# Hardware.net
KiCad netlist of a schematic drawn in EAGLE
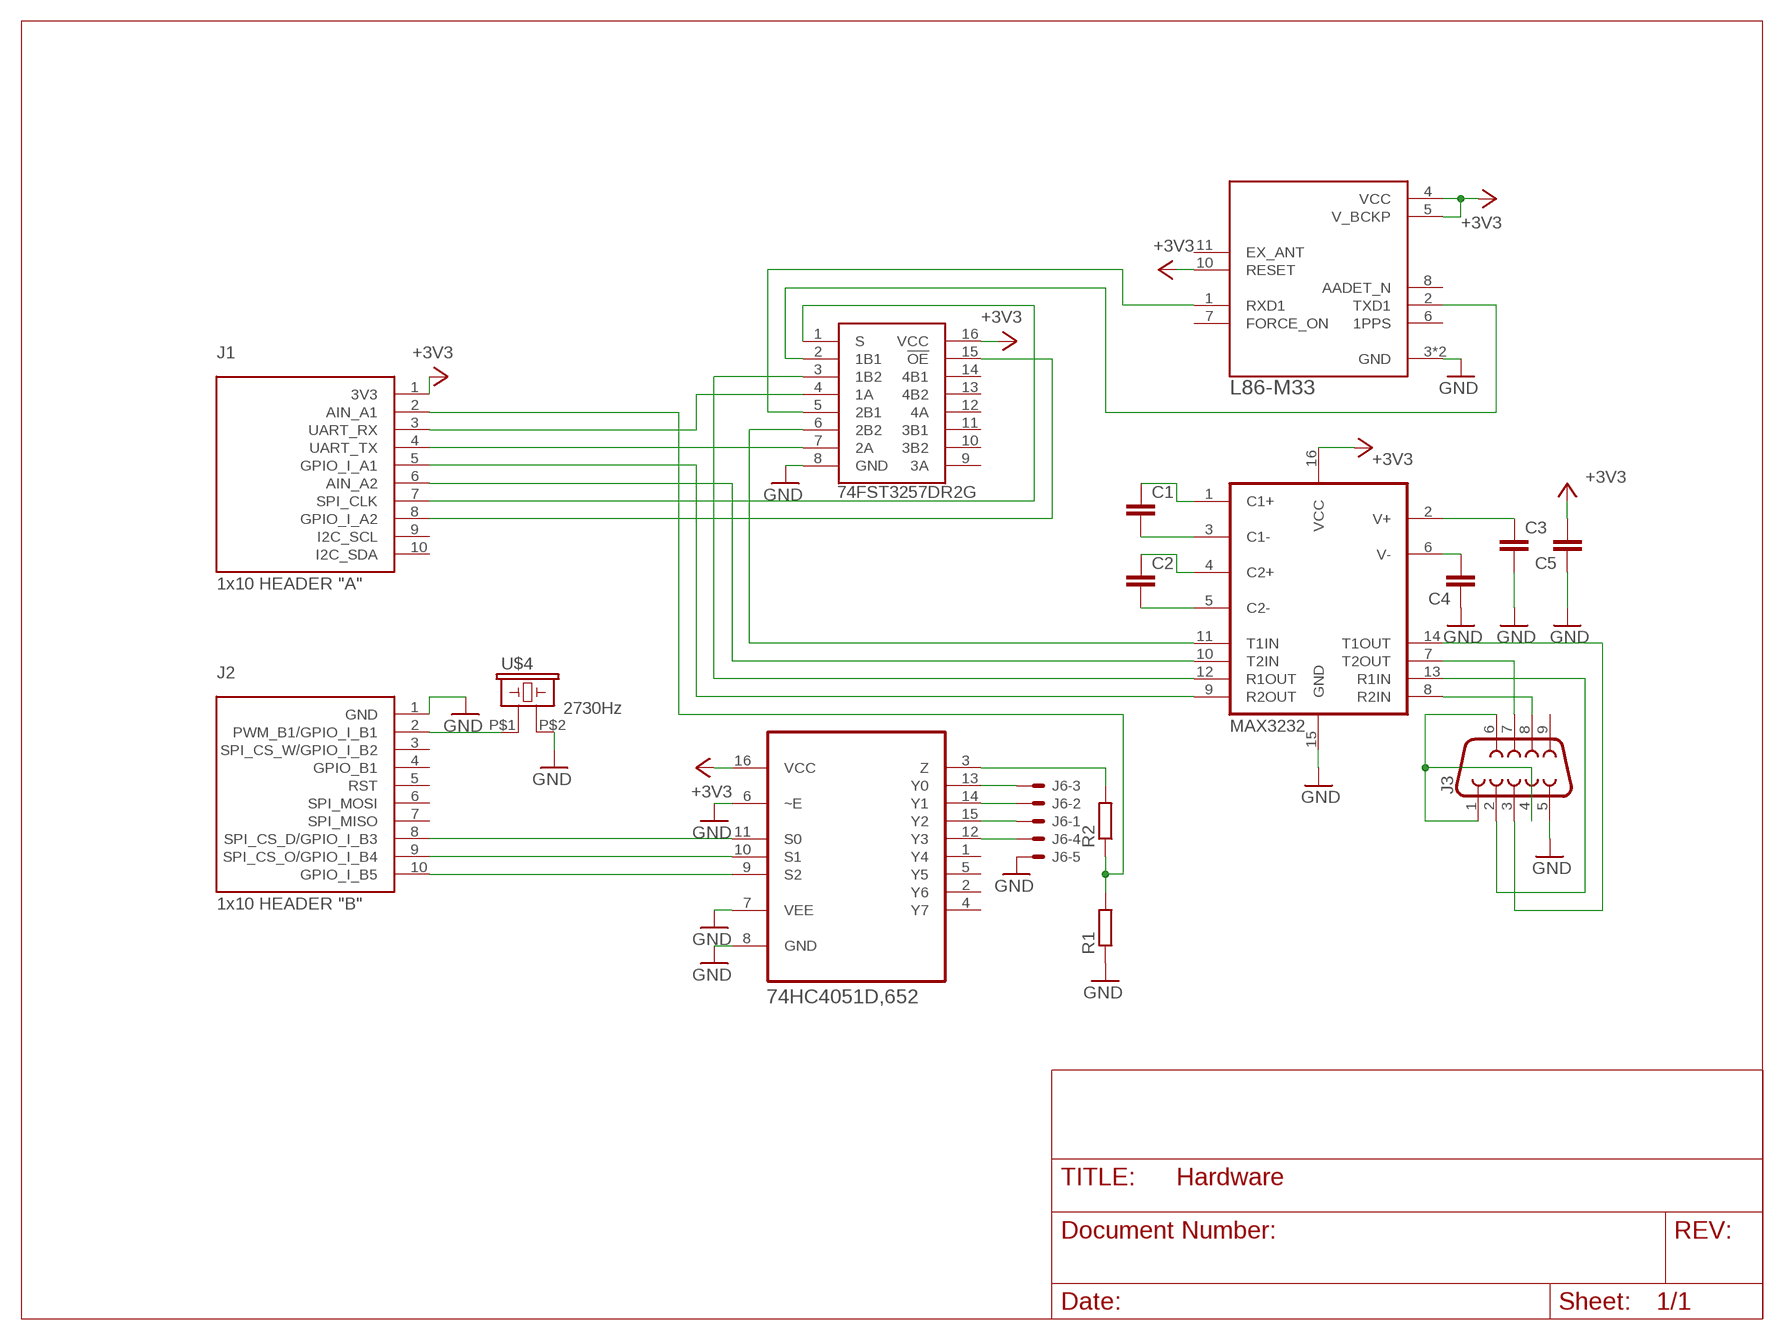
[diagram p0: schematic, sheet 1]

(export (version "E")
  (design (tool "Eeschema 10.0.6"))
  (components
    (comp (ref "C1")
      (value "C-EUC0805K")
      (footprint "eagle-import:C0805K")
      (libsource (lib "eagle-import") (part "C-EUC0805K"))
    )
    (comp (ref "C2")
      (value "C-EUC0805K")
      (footprint "eagle-import:C0805K")
      (libsource (lib "eagle-import") (part "C-EUC0805K"))
    )
    (comp (ref "C3")
      (value "C-EUC0805K")
      (footprint "eagle-import:C0805K")
      (libsource (lib "eagle-import") (part "C-EUC0805K"))
    )
    (comp (ref "C4")
      (value "C-EUC0805K")
      (footprint "eagle-import:C0805K")
      (libsource (lib "eagle-import") (part "C-EUC0805K"))
    )
    (comp (ref "C5")
      (value "C-EUC0805K")
      (footprint "eagle-import:C0805K")
      (libsource (lib "eagle-import") (part "C-EUC0805K"))
    )
    (comp (ref "IC1")
      (value "74FST3257DR2G")
      (footprint "eagle-import:SOIC127P600X175-16N")
      (fields (field (name "RS_PART_NUMBER") "8009395"))
      (libsource (lib "eagle-import") (part "74FST3257DR2G"))
    )
    (comp (ref "J1")
      (value "1x10 HEADER \"A\"")
      (footprint "eagle-import:1X10")
      (libsource (lib "eagle-import") (part "HEADER-1X10-J1"))
    )
    (comp (ref "J2")
      (value "1x10 HEADER \"B\"")
      (footprint "eagle-import:1X10")
      (libsource (lib "eagle-import") (part "HEADER-1X10-J2"))
    )
    (comp (ref "J3")
      (value "DB9MALE")
      (footprint "eagle-import:DB9_MALE")
      (libsource (lib "eagle-import") (part "DB9MALE"))
    )
    (comp (ref "J6")
      (value "22-27-2051-05")
      (footprint "eagle-import:6410-05")
      (fields (field (name "MF") "MOLEX"))
      (libsource (lib "eagle-import") (part "22-?-0527-2051"))
    )
    (comp (ref "R1")
      (value "R-EU_0207/7")
      (footprint "eagle-import:0207_7")
      (libsource (lib "eagle-import") (part "R-EU_0207/7"))
    )
    (comp (ref "R2")
      (value "R-EU_0207/7")
      (footprint "eagle-import:0207_7")
      (libsource (lib "eagle-import") (part "R-EU_0207/7"))
    )
    (comp (ref "U$4")
      (value "KCVG084B16")
      (footprint "eagle-import:KCVG084B16")
      (libsource (lib "eagle-import") (part "KCVG084B16"))
    )
    (comp (ref "U1")
      (value "MAX3232")
      (footprint "eagle-import:SO16")
      (libsource (lib "eagle-import") (part "MAX2323SOIC16"))
    )
    (comp (ref "U2")
      (value "L86-M33")
      (footprint "eagle-import:SON254P1840X1840X40-12N")
      (fields (field (name "MF") "Quectel"))
      (libsource (lib "eagle-import") (part "L86-M33"))
    )
    (comp (ref "U4")
      (value "74HC4051D,652")
      (footprint "eagle-import:SOIC127P600X175-16N")
      (fields (field (name "MF") "Nexperia"))
      (libsource (lib "eagle-import") (part "74HC4051D,652"))
    )
  )
  (nets
    (net (code "1") (name "+3V3") (class "Default")
      (node (ref "C5") (pin "2") (pinfunction "2_2") (pintype "passive"))
      (node (ref "IC1") (pin "16") (pinfunction "VCC_16") (pintype "input"))
      (node (ref "J1") (pin "1") (pinfunction "3V3_1") (pintype "bidirectional"))
      (node (ref "U1") (pin "16") (pinfunction "VCC_16") (pintype "bidirectional"))
      (node (ref "U2") (pin "10") (pinfunction "RESET_10") (pintype "input"))
      (node (ref "U2") (pin "4") (pinfunction "VCC_4") (pintype "power_in"))
      (node (ref "U2") (pin "5") (pinfunction "V_BCKP_5") (pintype "power_in"))
      (node (ref "U4") (pin "16") (pinfunction "VCC_16") (pintype "power_in"))
    )
    (net (code "2") (name "GND") (class "Default")
      (node (ref "C3") (pin "2") (pinfunction "2_2") (pintype "passive"))
      (node (ref "C4") (pin "1") (pinfunction "1_1") (pintype "passive"))
      (node (ref "C5") (pin "1") (pinfunction "1_1") (pintype "passive"))
      (node (ref "IC1") (pin "8") (pinfunction "GND_8") (pintype "input"))
      (node (ref "J2") (pin "1") (pinfunction "GND_1") (pintype "bidirectional"))
      (node (ref "J3") (pin "5") (pinfunction "5_5") (pintype "passive"))
      (node (ref "J6") (pin "5") (pinfunction "S_5") (pintype "passive"))
      (node (ref "R1") (pin "1") (pinfunction "1_1") (pintype "passive"))
      (node (ref "U$4") (pin "P$2") (pinfunction "2_P$2") (pintype "passive"))
      (node (ref "U1") (pin "15") (pinfunction "GND_15") (pintype "bidirectional"))
      (node (ref "U2") (pin "12") (pinfunction "GND_12") (pintype "passive"))
      (node (ref "U2") (pin "3") (pinfunction "GND_3") (pintype "passive"))
      (node (ref "U4") (pin "6") (pinfunction "~{E}_6") (pintype "input"))
      (node (ref "U4") (pin "7") (pinfunction "VEE_7") (pintype "power_in"))
      (node (ref "U4") (pin "8") (pinfunction "GND_8") (pintype "passive"))
    )
    (net (code "3") (name "Net-(IC1-1A)") (class "Default")
      (node (ref "IC1") (pin "4") (pinfunction "1A_4") (pintype "input"))
      (node (ref "J1") (pin "3") (pinfunction "UART_RX_3") (pintype "bidirectional"))
    )
    (net (code "4") (name "Net-(IC1-1B1)") (class "Default")
      (node (ref "IC1") (pin "2") (pinfunction "1B1_2") (pintype "input"))
      (node (ref "U2") (pin "2") (pinfunction "TXD1_2") (pintype "output"))
    )
    (net (code "5") (name "Net-(IC1-1B2)") (class "Default")
      (node (ref "IC1") (pin "3") (pinfunction "1B2_3") (pintype "input"))
      (node (ref "U1") (pin "12") (pinfunction "R1OUT_12") (pintype "output"))
    )
    (net (code "6") (name "Net-(IC1-2A)") (class "Default")
      (node (ref "IC1") (pin "7") (pinfunction "2A_7") (pintype "input"))
      (node (ref "J1") (pin "4") (pinfunction "UART_TX_4") (pintype "bidirectional"))
    )
    (net (code "7") (name "Net-(IC1-2B1)") (class "Default")
      (node (ref "IC1") (pin "5") (pinfunction "2B1_5") (pintype "input"))
      (node (ref "U2") (pin "1") (pinfunction "RXD1_1") (pintype "input"))
    )
    (net (code "8") (name "Net-(IC1-2B2)") (class "Default")
      (node (ref "IC1") (pin "6") (pinfunction "2B2_6") (pintype "input"))
      (node (ref "U1") (pin "11") (pinfunction "T1IN_11") (pintype "input"))
    )
    (net (code "9") (name "Net-(IC1-S)") (class "Default")
      (node (ref "IC1") (pin "1") (pinfunction "S_1") (pintype "input"))
      (node (ref "J1") (pin "7") (pinfunction "SPI_CLK_7") (pintype "bidirectional"))
    )
    (net (code "10") (name "Net-(IC1-~{OE})") (class "Default")
      (node (ref "IC1") (pin "15") (pinfunction "~{OE}_15") (pintype "input"))
      (node (ref "J1") (pin "8") (pinfunction "GPIO_I_A2_8") (pintype "bidirectional"))
    )
    (net (code "11") (name "Net-(J1-AIN_A1)") (class "Default")
      (node (ref "J1") (pin "2") (pinfunction "AIN_A1_2") (pintype "bidirectional"))
      (node (ref "R1") (pin "2") (pinfunction "2_2") (pintype "passive"))
      (node (ref "R2") (pin "1") (pinfunction "1_1") (pintype "passive"))
    )
    (net (code "12") (name "Net-(J1-AIN_A2)") (class "Default")
      (node (ref "J1") (pin "6") (pinfunction "AIN_A2_6") (pintype "bidirectional"))
      (node (ref "U1") (pin "10") (pinfunction "T2IN_10") (pintype "input"))
    )
    (net (code "13") (name "Net-(J1-GPIO_I_A1)") (class "Default")
      (node (ref "J1") (pin "5") (pinfunction "GPIO_I_A1_5") (pintype "bidirectional"))
      (node (ref "U1") (pin "9") (pinfunction "R2OUT_9") (pintype "output"))
    )
    (net (code "14") (name "Net-(J2-GPIO_I_B5)") (class "Default")
      (node (ref "J2") (pin "10") (pinfunction "GPIO_I_B5_10") (pintype "bidirectional"))
      (node (ref "U4") (pin "9") (pinfunction "S2_9") (pintype "input"))
    )
    (net (code "15") (name "Net-(J2-PWM_B1{slash}GPIO_I_B1)") (class "Default")
      (node (ref "J2") (pin "2") (pinfunction "PWM_B1/GPIO_I_B1_2") (pintype "bidirectional"))
      (node (ref "U$4") (pin "P$1") (pinfunction "1_P$1") (pintype "passive"))
    )
    (net (code "16") (name "Net-(J2-SPI_CS_D{slash}GPIO_I_B3)") (class "Default")
      (node (ref "J2") (pin "8") (pinfunction "SPI_CS_D/GPIO_I_B3_8") (pintype "bidirectional"))
      (node (ref "U4") (pin "11") (pinfunction "S0_11") (pintype "input"))
    )
    (net (code "17") (name "Net-(J2-SPI_CS_O{slash}GPIO_I_B4)") (class "Default")
      (node (ref "J2") (pin "9") (pinfunction "SPI_CS_O/GPIO_I_B4_9") (pintype "bidirectional"))
      (node (ref "U4") (pin "10") (pinfunction "S1_10") (pintype "input"))
    )
    (net (code "18") (name "Net-(J3-Pad1)") (class "Default")
      (node (ref "J3") (pin "1") (pinfunction "1_1") (pintype "passive"))
      (node (ref "J3") (pin "4") (pinfunction "4_4") (pintype "passive"))
      (node (ref "J3") (pin "6") (pinfunction "6_6") (pintype "passive"))
    )
    (net (code "19") (name "Net-(J6A-S)") (class "Default")
      (node (ref "J6") (pin "1") (pinfunction "S_1") (pintype "passive"))
      (node (ref "U4") (pin "15") (pinfunction "Y2_15") (pintype "bidirectional"))
    )
    (net (code "20") (name "Net-(J6B-S)") (class "Default")
      (node (ref "J6") (pin "2") (pinfunction "S_2") (pintype "passive"))
      (node (ref "U4") (pin "14") (pinfunction "Y1_14") (pintype "bidirectional"))
    )
    (net (code "21") (name "Net-(J6C-S)") (class "Default")
      (node (ref "J6") (pin "3") (pinfunction "S_3") (pintype "passive"))
      (node (ref "U4") (pin "13") (pinfunction "Y0_13") (pintype "bidirectional"))
    )
    (net (code "22") (name "Net-(J6D-S)") (class "Default")
      (node (ref "J6") (pin "4") (pinfunction "S_4") (pintype "passive"))
      (node (ref "U4") (pin "12") (pinfunction "Y3_12") (pintype "bidirectional"))
    )
    (net (code "23") (name "Net-(U1-C1+)") (class "Default")
      (node (ref "C1") (pin "1") (pinfunction "1_1") (pintype "passive"))
      (node (ref "U1") (pin "1") (pinfunction "C1+_1") (pintype "bidirectional"))
    )
    (net (code "24") (name "Net-(U1-C1-)") (class "Default")
      (node (ref "C1") (pin "2") (pinfunction "2_2") (pintype "passive"))
      (node (ref "U1") (pin "3") (pinfunction "C1-_3") (pintype "bidirectional"))
    )
    (net (code "25") (name "Net-(U1-C2+)") (class "Default")
      (node (ref "C2") (pin "1") (pinfunction "1_1") (pintype "passive"))
      (node (ref "U1") (pin "4") (pinfunction "C2+_4") (pintype "bidirectional"))
    )
    (net (code "26") (name "Net-(U1-C2-)") (class "Default")
      (node (ref "C2") (pin "2") (pinfunction "2_2") (pintype "passive"))
      (node (ref "U1") (pin "5") (pinfunction "C2-_5") (pintype "bidirectional"))
    )
    (net (code "27") (name "Net-(U1-R1IN)") (class "Default")
      (node (ref "J3") (pin "2") (pinfunction "2_2") (pintype "passive"))
      (node (ref "U1") (pin "13") (pinfunction "R1IN_13") (pintype "input"))
    )
    (net (code "28") (name "Net-(U1-R2IN)") (class "Default")
      (node (ref "J3") (pin "8") (pinfunction "8_8") (pintype "passive"))
      (node (ref "U1") (pin "8") (pinfunction "R2IN_8") (pintype "input"))
    )
    (net (code "29") (name "Net-(U1-T1OUT)") (class "Default")
      (node (ref "J3") (pin "3") (pinfunction "3_3") (pintype "passive"))
      (node (ref "U1") (pin "14") (pinfunction "T1OUT_14") (pintype "output"))
    )
    (net (code "30") (name "Net-(U1-T2OUT)") (class "Default")
      (node (ref "J3") (pin "7") (pinfunction "7_7") (pintype "passive"))
      (node (ref "U1") (pin "7") (pinfunction "T2OUT_7") (pintype "output"))
    )
    (net (code "31") (name "Net-(U1-V+)") (class "Default")
      (node (ref "C3") (pin "1") (pinfunction "1_1") (pintype "passive"))
      (node (ref "U1") (pin "2") (pinfunction "V+_2") (pintype "bidirectional"))
    )
    (net (code "32") (name "Net-(U1-V-)") (class "Default")
      (node (ref "C4") (pin "2") (pinfunction "2_2") (pintype "passive"))
      (node (ref "U1") (pin "6") (pinfunction "V-_6") (pintype "bidirectional"))
    )
    (net (code "33") (name "Net-(U4-Z)") (class "Default")
      (node (ref "R2") (pin "2") (pinfunction "2_2") (pintype "passive"))
      (node (ref "U4") (pin "3") (pinfunction "Z_3") (pintype "bidirectional"))
    )
    (net (code "34") (name "unconnected-(IC1-3A-Pad9)") (class "Default")
      (node (ref "IC1") (pin "9") (pinfunction "3A_9") (pintype "input"))
    )
    (net (code "35") (name "unconnected-(IC1-3B1-Pad11)") (class "Default")
      (node (ref "IC1") (pin "11") (pinfunction "3B1_11") (pintype "input"))
    )
    (net (code "36") (name "unconnected-(IC1-3B2-Pad10)") (class "Default")
      (node (ref "IC1") (pin "10") (pinfunction "3B2_10") (pintype "input"))
    )
    (net (code "37") (name "unconnected-(IC1-4A-Pad12)") (class "Default")
      (node (ref "IC1") (pin "12") (pinfunction "4A_12") (pintype "input"))
    )
    (net (code "38") (name "unconnected-(IC1-4B1-Pad14)") (class "Default")
      (node (ref "IC1") (pin "14") (pinfunction "4B1_14") (pintype "input"))
    )
    (net (code "39") (name "unconnected-(IC1-4B2-Pad13)") (class "Default")
      (node (ref "IC1") (pin "13") (pinfunction "4B2_13") (pintype "input"))
    )
    (net (code "40") (name "unconnected-(J1-I2C_SCL-Pad9)") (class "Default")
      (node (ref "J1") (pin "9") (pinfunction "I2C_SCL_9") (pintype "bidirectional"))
    )
    (net (code "41") (name "unconnected-(J1-I2C_SDA-Pad10)") (class "Default")
      (node (ref "J1") (pin "10") (pinfunction "I2C_SDA_10") (pintype "bidirectional"))
    )
    (net (code "42") (name "unconnected-(J2-GPIO_B1-Pad4)") (class "Default")
      (node (ref "J2") (pin "4") (pinfunction "GPIO_B1_4") (pintype "bidirectional"))
    )
    (net (code "43") (name "unconnected-(J2-RST-Pad5)") (class "Default")
      (node (ref "J2") (pin "5") (pinfunction "RST_5") (pintype "bidirectional"))
    )
    (net (code "44") (name "unconnected-(J2-SPI_CS_W{slash}GPIO_I_B2-Pad3)") (class "Default")
      (node (ref "J2") (pin "3") (pinfunction "SPI_CS_W/GPIO_I_B2_3") (pintype "bidirectional"))
    )
    (net (code "45") (name "unconnected-(J2-SPI_MISO-Pad7)") (class "Default")
      (node (ref "J2") (pin "7") (pinfunction "SPI_MISO_7") (pintype "bidirectional"))
    )
    (net (code "46") (name "unconnected-(J2-SPI_MOSI-Pad6)") (class "Default")
      (node (ref "J2") (pin "6") (pinfunction "SPI_MOSI_6") (pintype "bidirectional"))
    )
    (net (code "47") (name "unconnected-(J3-Pad9)") (class "Default")
      (node (ref "J3") (pin "9") (pinfunction "9_9") (pintype "passive"))
    )
    (net (code "48") (name "unconnected-(U2-1PPS-Pad6)") (class "Default")
      (node (ref "U2") (pin "6") (pinfunction "1PPS_6") (pintype "output"))
    )
    (net (code "49") (name "unconnected-(U2-AADET_N-Pad8)") (class "Default")
      (node (ref "U2") (pin "8") (pinfunction "AADET_N_8") (pintype "output"))
    )
    (net (code "50") (name "unconnected-(U2-EX_ANT-Pad11)") (class "Default")
      (node (ref "U2") (pin "11") (pinfunction "EX_ANT_11") (pintype "input"))
    )
    (net (code "51") (name "unconnected-(U2-FORCE_ON-Pad7)") (class "Default")
      (node (ref "U2") (pin "7") (pinfunction "FORCE_ON_7") (pintype "input"))
    )
    (net (code "52") (name "unconnected-(U4-Y4-Pad1)") (class "Default")
      (node (ref "U4") (pin "1") (pinfunction "Y4_1") (pintype "bidirectional"))
    )
    (net (code "53") (name "unconnected-(U4-Y5-Pad5)") (class "Default")
      (node (ref "U4") (pin "5") (pinfunction "Y5_5") (pintype "bidirectional"))
    )
    (net (code "54") (name "unconnected-(U4-Y6-Pad2)") (class "Default")
      (node (ref "U4") (pin "2") (pinfunction "Y6_2") (pintype "bidirectional"))
    )
    (net (code "55") (name "unconnected-(U4-Y7-Pad4)") (class "Default")
      (node (ref "U4") (pin "4") (pinfunction "Y7_4") (pintype "bidirectional"))
    )
  )
)
